# Microcontroller.net
KiCad netlist of a schematic drawn in Altium Designer
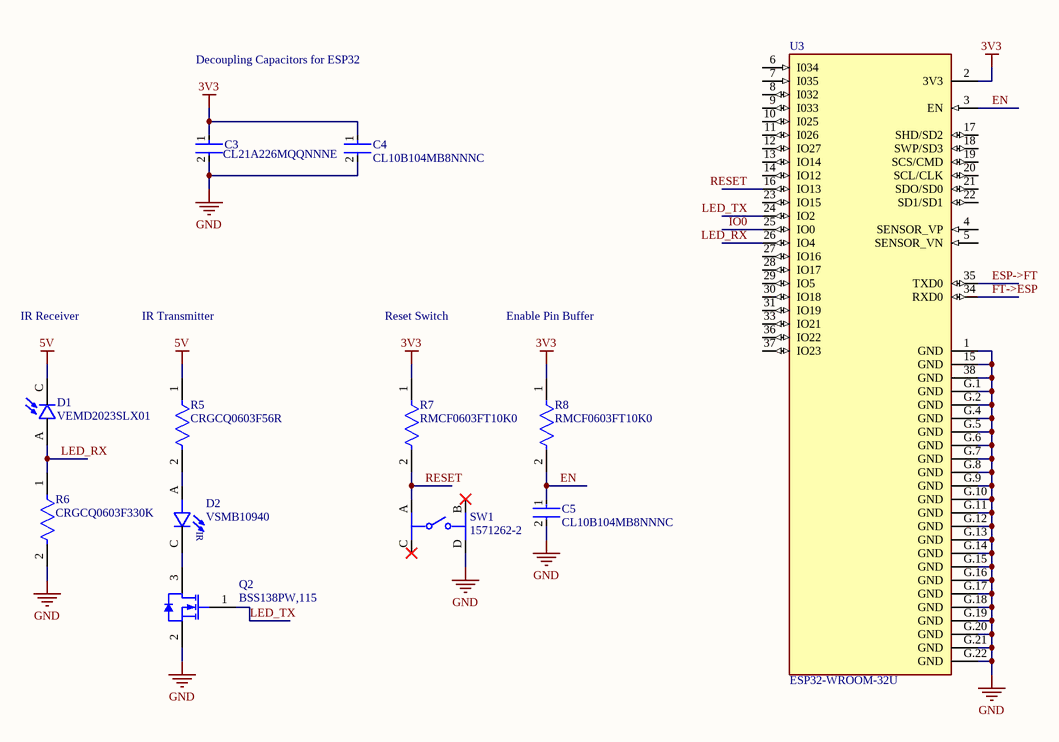
[diagram p0: Microcontroller.SchDoc]

(export (version "E")
  (design (tool "Eeschema 10.0.6"))
  (components
    (comp (ref "C3")
      (value "CL21A226MQQNNNE")
      (footprint "FP-CL21-IPC_A")
      (description "CL21 Series 0805 22uF 6.3V ±20% Tolerance X5R Multilayer Ceramic Chip Capacitor")
      (fields (field (name "TOLERANCE") "20%"))
      (libsource (lib "Altium Content Vault") (part "b4654b650e69147ec39a6b967a45e02"))
    )
    (comp (ref "C4")
      (value "CL10B104MB8NNNC")
      (footprint "FP-CL10-IPC_C")
      (description "Cap Ceramic 100nF 50V X7R ±20% Pad SMD 0603 +125°C T/R")
      (fields (field (name "TOLERANCE") "20%"))
      (libsource (lib "Altium Content Vault") (part "b4654b650e69147ec39a6b967a45e02"))
    )
    (comp (ref "C5")
      (value "CL10B104MB8NNNC")
      (footprint "FP-CL10-IPC_C")
      (description "Cap Ceramic 100nF 50V X7R ±20% Pad SMD 0603 +125°C T/R")
      (fields (field (name "TOLERANCE") "20%"))
      (libsource (lib "Altium Content Vault") (part "b4654b650e69147ec39a6b967a45e02"))
    )
    (comp (ref "D1")
      (value "VEMD2023SLX01")
      (footprint "VEMD2023SLX01:XDCR_VEMD2023SLX01")
      (fields (field (name "MF") "{'manufacturer': u'Vishay Semiconductor'}"))
      (libsource (lib "*") (part "VEMD2023SLX01"))
    )
    (comp (ref "D2")
      (value "VSMB10940")
      (footprint "VSMB10940:DIO_VSMB10940")
      (description "940 nm 65 mA Â±75Â° Surface Mount High Speed Infrared Emitting Diode")
      (fields (field (name "MF") "{'manufacturer': u'Vishay Semiconductor'}"))
      (libsource (lib "*") (part "VSMB10940"))
    )
    (comp (ref "Q2")
      (value "BSS138PW,115")
      (footprint "NXP-SOT323_M")
      (description "N-Channel Trench MOSFET, 60 V, 0.32 A, -55 to 150 degC, 3-Pin SOT323, Tape and Reel")
      (fields (field (name "MANUFACTURER") "NXP Semiconductors"))
      (libsource (lib "Altium Content Vault") (part "NXP-NMOS-GSD-3_B"))
    )
    (comp (ref "R5")
      (value "CRGCQ0603F56R")
      (footprint "FP-CRGCQ0603-IPC_C")
      (description "CRGCQ0603 56Ω 1% ±200ppm/°C 75V")
      (fields (field (name "MANUFACTURER") "TE Connectivity") (field (name "TOLERANCE") "0.01"))
      (libsource (lib "Altium Content Vault") (part "1029c3af85768c4190bb7ad29bc67b5"))
    )
    (comp (ref "R6")
      (value "CRGCQ0603F330K")
      (footprint "FP-CRGCQ0603-IPC_C")
      (description "Res Thick Film 0603 330K Ohm 1% 0.1W(1/10W) ±100ppm/C Pad SMD Automotive T/R")
      (fields (field (name "MANUFACTURER") "TE Connectivity") (field (name "TOLERANCE") "0.01"))
      (libsource (lib "Altium Content Vault") (part "1029c3af85768c4190bb7ad29bc67b5"))
    )
    (comp (ref "R7")
      (value "RMCF0603FT10K0")
      (footprint "FP-RMCF0603-MFG")
      (description "10kΩ ±1% 0.1W 0603 Thick Film Chip Resistor AEC-Q200 compliant")
      (fields (field (name "TOLERANCE") "1%"))
      (libsource (lib "Altium Content Vault") (part "1029c3af85768c4190bb7ad29bc67b5"))
    )
    (comp (ref "R8")
      (value "RMCF0603FT10K0")
      (footprint "FP-RMCF0603-MFG")
      (description "10kΩ ±1% 0.1W 0603 Thick Film Chip Resistor AEC-Q200 compliant")
      (fields (field (name "TOLERANCE") "1%"))
      (libsource (lib "Altium Content Vault") (part "1029c3af85768c4190bb7ad29bc67b5"))
    )
    (comp (ref "SW1")
      (value "1571262-2")
      (footprint "FP-1571262-2-MFG")
      (description "SWITCH TACTILE SPST-NO 0.05A 12V")
      (libsource (lib "Altium Content Vault") (part "7af1e63d87958053304b0ff27c3d6bc"))
    )
    (comp (ref "U3")
      (value "ESP32-WROOM-32U")
      (footprint "ESP32-WROOM-32U:XCVR_ESP32-WROOM-32U")
      (description "Wi-Fi/BT BLE Module ESP32-D0WD SPI Flash UART U.FL Conn.")
      (fields (field (name "MF") "{'manufacturer': u'Espressif Systems'}"))
      (libsource (lib "*") (part "ESP32-WROOM-32U"))
    )
  )
  (nets
    (net (code "1") (name "/EN") (class "Default")
      (node (ref "C5") (pin "1") (pinfunction "1_1") (pintype "passive"))
      (node (ref "R8") (pin "2") (pinfunction "2_2") (pintype "passive"))
      (node (ref "U3") (pin "3") (pinfunction "EN_3") (pintype "input"))
    )
    (net (code "2") (name "/ESP->FT") (class "Default")
      (node (ref "U3") (pin "35") (pinfunction "TXD0_35") (pintype "bidirectional"))
    )
    (net (code "3") (name "/FT->ESP") (class "Default")
      (node (ref "U3") (pin "34") (pinfunction "RXD0_34") (pintype "bidirectional"))
    )
    (net (code "4") (name "/IO0") (class "Default")
      (node (ref "U3") (pin "25") (pinfunction "IO0_25") (pintype "bidirectional"))
    )
    (net (code "5") (name "/LED_RX") (class "Default")
      (node (ref "D1") (pin "A") (pinfunction "A_A") (pintype "passive"))
      (node (ref "R6") (pin "1") (pinfunction "1_1") (pintype "passive"))
      (node (ref "U3") (pin "26") (pinfunction "IO4_26") (pintype "bidirectional"))
    )
    (net (code "6") (name "/LED_TX") (class "Default")
      (node (ref "Q2") (pin "1") (pinfunction "G_1") (pintype "passive"))
      (node (ref "U3") (pin "24") (pinfunction "IO2_24") (pintype "bidirectional"))
    )
    (net (code "7") (name "/RESET") (class "Default")
      (node (ref "R7") (pin "2") (pinfunction "2_2") (pintype "passive"))
      (node (ref "SW1") (pin "A") (pinfunction "A_A") (pintype "passive"))
      (node (ref "U3") (pin "16") (pinfunction "IO13_16") (pintype "bidirectional"))
    )
    (net (code "8") (name "3V3") (class "Default")
      (node (ref "C3") (pin "1") (pinfunction "1_1") (pintype "passive"))
      (node (ref "C4") (pin "1") (pinfunction "1_1") (pintype "passive"))
      (node (ref "R7") (pin "1") (pinfunction "1_1") (pintype "passive"))
      (node (ref "R8") (pin "1") (pinfunction "1_1") (pintype "passive"))
      (node (ref "U3") (pin "2") (pinfunction "3V3_2") (pintype "power_in"))
    )
    (net (code "9") (name "5V") (class "Default")
      (node (ref "D1") (pin "C") (pinfunction "C_C") (pintype "passive"))
      (node (ref "R5") (pin "1") (pinfunction "1_1") (pintype "passive"))
    )
    (net (code "10") (name "GND") (class "Default")
      (node (ref "C3") (pin "2") (pinfunction "2_2") (pintype "passive"))
      (node (ref "C4") (pin "2") (pinfunction "2_2") (pintype "passive"))
      (node (ref "C5") (pin "2") (pinfunction "2_2") (pintype "passive"))
      (node (ref "Q2") (pin "2") (pinfunction "S_2") (pintype "passive"))
      (node (ref "R6") (pin "2") (pinfunction "2_2") (pintype "passive"))
      (node (ref "SW1") (pin "D") (pinfunction "D_D") (pintype "passive"))
      (node (ref "U3") (pin "1") (pinfunction "GND_1") (pintype "power_in"))
      (node (ref "U3") (pin "15") (pinfunction "GND_15") (pintype "power_in"))
      (node (ref "U3") (pin "38") (pinfunction "GND_38") (pintype "power_in"))
      (node (ref "U3") (pin "G.1") (pinfunction "GND_G.1") (pintype "power_in"))
      (node (ref "U3") (pin "G.10") (pinfunction "GND_G.10") (pintype "power_in"))
      (node (ref "U3") (pin "G.11") (pinfunction "GND_G.11") (pintype "power_in"))
      (node (ref "U3") (pin "G.12") (pinfunction "GND_G.12") (pintype "power_in"))
      (node (ref "U3") (pin "G.13") (pinfunction "GND_G.13") (pintype "power_in"))
      (node (ref "U3") (pin "G.14") (pinfunction "GND_G.14") (pintype "power_in"))
      (node (ref "U3") (pin "G.15") (pinfunction "GND_G.15") (pintype "power_in"))
      (node (ref "U3") (pin "G.16") (pinfunction "GND_G.16") (pintype "power_in"))
      (node (ref "U3") (pin "G.17") (pinfunction "GND_G.17") (pintype "power_in"))
      (node (ref "U3") (pin "G.18") (pinfunction "GND_G.18") (pintype "power_in"))
      (node (ref "U3") (pin "G.19") (pinfunction "GND_G.19") (pintype "power_in"))
      (node (ref "U3") (pin "G.2") (pinfunction "GND_G.2") (pintype "power_in"))
      (node (ref "U3") (pin "G.20") (pinfunction "GND_G.20") (pintype "power_in"))
      (node (ref "U3") (pin "G.21") (pinfunction "GND_G.21") (pintype "power_in"))
      (node (ref "U3") (pin "G.22") (pinfunction "GND_G.22") (pintype "power_in"))
      (node (ref "U3") (pin "G.4") (pinfunction "GND_G.4") (pintype "power_in"))
      (node (ref "U3") (pin "G.5") (pinfunction "GND_G.5") (pintype "power_in"))
      (node (ref "U3") (pin "G.6") (pinfunction "GND_G.6") (pintype "power_in"))
      (node (ref "U3") (pin "G.7") (pinfunction "GND_G.7") (pintype "power_in"))
      (node (ref "U3") (pin "G.8") (pinfunction "GND_G.8") (pintype "power_in"))
      (node (ref "U3") (pin "G.9") (pinfunction "GND_G.9") (pintype "power_in"))
    )
    (net (code "11") (name "Net-(D2-PadA)") (class "Default")
      (node (ref "D2") (pin "A") (pinfunction "A_A") (pintype "passive"))
      (node (ref "R5") (pin "2") (pinfunction "2_2") (pintype "passive"))
    )
    (net (code "12") (name "Net-(Q2-D)") (class "Default")
      (node (ref "D2") (pin "C") (pinfunction "C_C") (pintype "passive"))
      (node (ref "Q2") (pin "3") (pinfunction "D_3") (pintype "passive"))
    )
    (net (code "13") (name "unconnected-(SW1-PadB)") (class "Default")
      (node (ref "SW1") (pin "B") (pinfunction "B_B") (pintype "passive+no_connect"))
    )
    (net (code "14") (name "unconnected-(SW1-PadC)") (class "Default")
      (node (ref "SW1") (pin "C") (pinfunction "C_C") (pintype "passive+no_connect"))
    )
    (net (code "15") (name "unconnected-(U3-I025-Pad10)") (class "Default")
      (node (ref "U3") (pin "10") (pinfunction "I025_10") (pintype "bidirectional"))
    )
    (net (code "16") (name "unconnected-(U3-I026-Pad11)") (class "Default")
      (node (ref "U3") (pin "11") (pinfunction "I026_11") (pintype "bidirectional"))
    )
    (net (code "17") (name "unconnected-(U3-I032-Pad8)") (class "Default")
      (node (ref "U3") (pin "8") (pinfunction "I032_8") (pintype "bidirectional"))
    )
    (net (code "18") (name "unconnected-(U3-I033-Pad9)") (class "Default")
      (node (ref "U3") (pin "9") (pinfunction "I033_9") (pintype "bidirectional"))
    )
    (net (code "19") (name "unconnected-(U3-I034-Pad6)") (class "Default")
      (node (ref "U3") (pin "6") (pinfunction "I034_6") (pintype "input"))
    )
    (net (code "20") (name "unconnected-(U3-I035-Pad7)") (class "Default")
      (node (ref "U3") (pin "7") (pinfunction "I035_7") (pintype "input"))
    )
    (net (code "21") (name "unconnected-(U3-IO5-Pad29)") (class "Default")
      (node (ref "U3") (pin "29") (pinfunction "IO5_29") (pintype "bidirectional"))
    )
    (net (code "22") (name "unconnected-(U3-IO12-Pad14)") (class "Default")
      (node (ref "U3") (pin "14") (pinfunction "IO12_14") (pintype "bidirectional"))
    )
    (net (code "23") (name "unconnected-(U3-IO14-Pad13)") (class "Default")
      (node (ref "U3") (pin "13") (pinfunction "IO14_13") (pintype "bidirectional"))
    )
    (net (code "24") (name "unconnected-(U3-IO15-Pad23)") (class "Default")
      (node (ref "U3") (pin "23") (pinfunction "IO15_23") (pintype "bidirectional"))
    )
    (net (code "25") (name "unconnected-(U3-IO16-Pad27)") (class "Default")
      (node (ref "U3") (pin "27") (pinfunction "IO16_27") (pintype "bidirectional"))
    )
    (net (code "26") (name "unconnected-(U3-IO17-Pad28)") (class "Default")
      (node (ref "U3") (pin "28") (pinfunction "IO17_28") (pintype "bidirectional"))
    )
    (net (code "27") (name "unconnected-(U3-IO18-Pad30)") (class "Default")
      (node (ref "U3") (pin "30") (pinfunction "IO18_30") (pintype "bidirectional"))
    )
    (net (code "28") (name "unconnected-(U3-IO19-Pad31)") (class "Default")
      (node (ref "U3") (pin "31") (pinfunction "IO19_31") (pintype "bidirectional"))
    )
    (net (code "29") (name "unconnected-(U3-IO21-Pad33)") (class "Default")
      (node (ref "U3") (pin "33") (pinfunction "IO21_33") (pintype "bidirectional"))
    )
    (net (code "30") (name "unconnected-(U3-IO22-Pad36)") (class "Default")
      (node (ref "U3") (pin "36") (pinfunction "IO22_36") (pintype "bidirectional"))
    )
    (net (code "31") (name "unconnected-(U3-IO23-Pad37)") (class "Default")
      (node (ref "U3") (pin "37") (pinfunction "IO23_37") (pintype "bidirectional"))
    )
    (net (code "32") (name "unconnected-(U3-IO27-Pad12)") (class "Default")
      (node (ref "U3") (pin "12") (pinfunction "IO27_12") (pintype "bidirectional"))
    )
    (net (code "33") (name "unconnected-(U3-SCL{slash}CLK-Pad20)") (class "Default")
      (node (ref "U3") (pin "20") (pinfunction "SCL/CLK_20") (pintype "bidirectional"))
    )
    (net (code "34") (name "unconnected-(U3-SCS{slash}CMD-Pad19)") (class "Default")
      (node (ref "U3") (pin "19") (pinfunction "SCS/CMD_19") (pintype "bidirectional"))
    )
    (net (code "35") (name "unconnected-(U3-SD1{slash}SD1-Pad22)") (class "Default")
      (node (ref "U3") (pin "22") (pinfunction "SD1/SD1_22") (pintype "bidirectional"))
    )
    (net (code "36") (name "unconnected-(U3-SDO{slash}SD0-Pad21)") (class "Default")
      (node (ref "U3") (pin "21") (pinfunction "SDO/SD0_21") (pintype "bidirectional"))
    )
    (net (code "37") (name "unconnected-(U3-SENSOR_VN-Pad5)") (class "Default")
      (node (ref "U3") (pin "5") (pinfunction "SENSOR_VN_5") (pintype "input"))
    )
    (net (code "38") (name "unconnected-(U3-SENSOR_VP-Pad4)") (class "Default")
      (node (ref "U3") (pin "4") (pinfunction "SENSOR_VP_4") (pintype "input"))
    )
    (net (code "39") (name "unconnected-(U3-SHD{slash}SD2-Pad17)") (class "Default")
      (node (ref "U3") (pin "17") (pinfunction "SHD/SD2_17") (pintype "bidirectional"))
    )
    (net (code "40") (name "unconnected-(U3-SWP{slash}SD3-Pad18)") (class "Default")
      (node (ref "U3") (pin "18") (pinfunction "SWP/SD3_18") (pintype "bidirectional"))
    )
  )
)
